# Lightsaber.net
KiCad netlist of a schematic drawn in EasyEDA
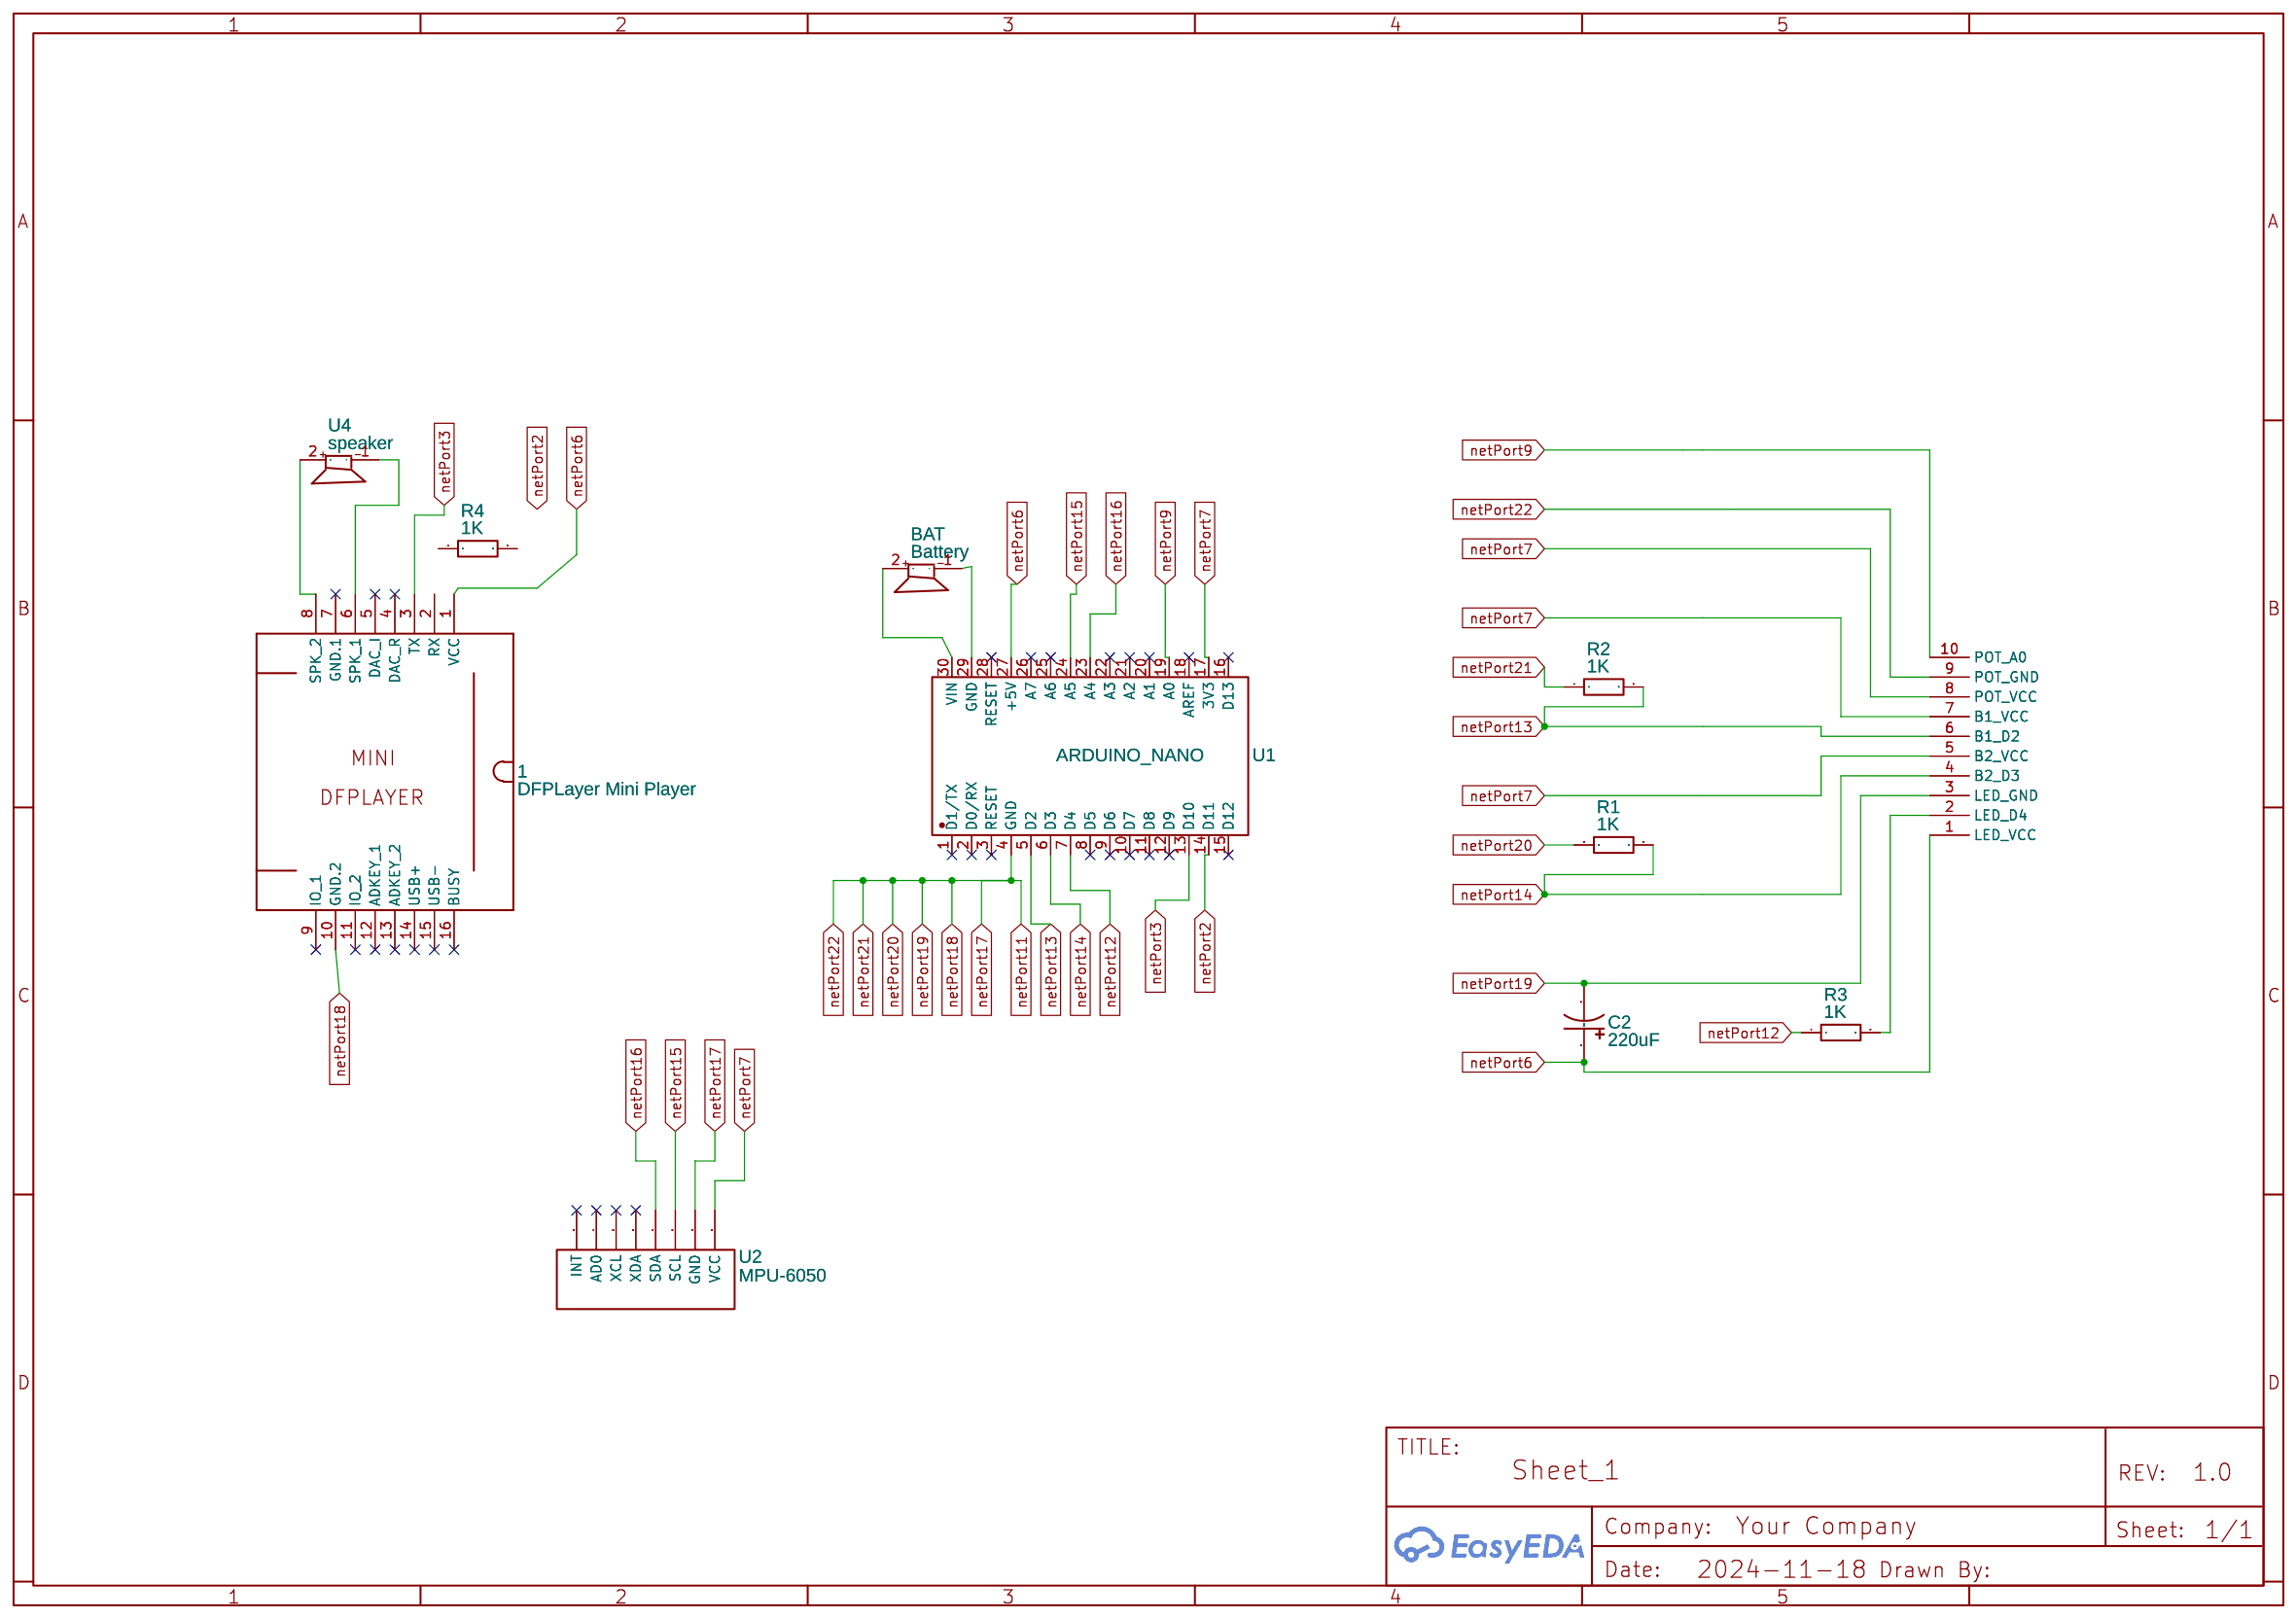
[diagram p0: schematic sheet]

(export (version "E")
  (design (tool "Eeschema 10.0.6"))
  (components
    (comp (ref "1")
      (value "DFPLayer Mini Player")
      (fields (field (name "Manufacturer") "DFP"))
      (libsource (lib "") (part "DFPLayer Mini Player"))
    )
    (comp (ref "BAT") (value "Battery") (libsource (lib "") (part "speaker")))
    (comp (ref "C2") (value "220uF") (libsource (lib "") (part "capacitor 220uF @ 16V")))
    (comp (ref "P1")
      (value "10 pins")
      (fields (field (name "Manufacturer Part") "New SchematicLib"))
      (libsource (lib "") (part "10 pins"))
    )
    (comp (ref "R1")
      (value "1K")
      (fields (field (name "Manufacturer Part") "0.125Wt_k"))
      (libsource (lib "") (part "0.125Wt_d"))
    )
    (comp (ref "R2")
      (value "1K")
      (fields (field (name "Manufacturer Part") "0.125Wt_k"))
      (libsource (lib "") (part "0.125Wt_d"))
    )
    (comp (ref "R3")
      (value "1K")
      (fields (field (name "Manufacturer Part") "0.125Wt_k"))
      (libsource (lib "") (part "0.125Wt_d"))
    )
    (comp (ref "R4")
      (value "1K")
      (fields (field (name "Manufacturer Part") "0.125Wt_k"))
      (libsource (lib "") (part "0.125Wt_d"))
    )
    (comp (ref "U1") (value "ARDUINO_NANO") (libsource (lib "") (part "ARDUINO_NANO")))
    (comp (ref "U2") (value "MPU-6050") (libsource (lib "") (part "MPU-6050")))
    (comp (ref "U4") (value "speaker") (libsource (lib "") (part "speaker_1")))
  )
  (nets
    (net (code "1") (name "Net-(1-SPK_1)") (class "Default")
      (node (ref "1") (pin "6") (pinfunction "SPK_1_6") (pintype "bidirectional"))
      (node (ref "U4") (pin "1") (pinfunction "-_1") (pintype "unspecified"))
    )
    (net (code "2") (name "Net-(1-SPK_2)") (class "Default")
      (node (ref "1") (pin "8") (pinfunction "SPK_2_8") (pintype "bidirectional"))
      (node (ref "U4") (pin "2") (pinfunction "+_2") (pintype "unspecified"))
    )
    (net (code "3") (name "Net-(BAT-+)") (class "Default")
      (node (ref "BAT") (pin "2") (pinfunction "+_2") (pintype "unspecified"))
      (node (ref "U1") (pin "30") (pinfunction "VIN_30") (pintype "unspecified"))
    )
    (net (code "4") (name "Net-(BAT--)") (class "Default")
      (node (ref "BAT") (pin "1") (pinfunction "-_1") (pintype "unspecified"))
      (node (ref "U1") (pin "29") (pinfunction "GND_29") (pintype "unspecified"))
    )
    (net (code "5") (name "Net-(P1-LED_D4)") (class "Default")
      (node (ref "P1") (pin "2") (pinfunction "LED_D4_2") (pintype "unspecified"))
      (node (ref "R3") (pin "2") (pinfunction "2_2") (pintype "unspecified"))
    )
    (net (code "6") (name "netPort2") (class "Default")
      (node (ref "U1") (pin "14") (pinfunction "D11_14") (pintype "unspecified"))
    )
    (net (code "7") (name "netPort3") (class "Default")
      (node (ref "1") (pin "3") (pinfunction "TX_3") (pintype "bidirectional"))
      (node (ref "U1") (pin "13") (pinfunction "D10_13") (pintype "unspecified"))
    )
    (net (code "8") (name "netPort6") (class "Default")
      (node (ref "1") (pin "1") (pinfunction "VCC_1") (pintype "bidirectional"))
      (node (ref "C2") (pin "1") (pinfunction "1_1") (pintype "unspecified"))
      (node (ref "P1") (pin "1") (pinfunction "LED_VCC_1") (pintype "unspecified"))
      (node (ref "U1") (pin "27") (pinfunction "+5V_27") (pintype "unspecified"))
    )
    (net (code "9") (name "netPort7") (class "Default")
      (node (ref "P1") (pin "5") (pinfunction "B2_VCC_5") (pintype "unspecified"))
      (node (ref "P1") (pin "7") (pinfunction "B1_VCC_7") (pintype "unspecified"))
      (node (ref "P1") (pin "8") (pinfunction "POT_VCC_8") (pintype "unspecified"))
      (node (ref "U1") (pin "17") (pinfunction "3V3_17") (pintype "unspecified"))
      (node (ref "U2") (pin "1") (pinfunction "VCC_1") (pintype "unspecified"))
    )
    (net (code "10") (name "netPort9") (class "Default")
      (node (ref "P1") (pin "10") (pinfunction "POT_A0_10") (pintype "unspecified"))
      (node (ref "U1") (pin "19") (pinfunction "A0_19") (pintype "unspecified"))
    )
    (net (code "11") (name "netPort11") (class "Default")
      (node (ref "1") (pin "10") (pinfunction "GND.2_10") (pintype "bidirectional"))
      (node (ref "C2") (pin "2") (pinfunction "2_2") (pintype "unspecified"))
      (node (ref "P1") (pin "3") (pinfunction "LED_GND_3") (pintype "unspecified"))
      (node (ref "P1") (pin "9") (pinfunction "POT_GND_9") (pintype "unspecified"))
      (node (ref "R1") (pin "1") (pinfunction "1_1") (pintype "unspecified"))
      (node (ref "R2") (pin "1") (pinfunction "1_1") (pintype "unspecified"))
      (node (ref "U1") (pin "4") (pinfunction "GND_4") (pintype "unspecified"))
      (node (ref "U2") (pin "2") (pinfunction "GND_2") (pintype "unspecified"))
    )
    (net (code "12") (name "netPort12") (class "Default")
      (node (ref "R3") (pin "1") (pinfunction "1_1") (pintype "unspecified"))
      (node (ref "U1") (pin "7") (pinfunction "D4_7") (pintype "unspecified"))
    )
    (net (code "13") (name "netPort13") (class "Default")
      (node (ref "P1") (pin "6") (pinfunction "B1_D2_6") (pintype "unspecified"))
      (node (ref "R2") (pin "2") (pinfunction "2_2") (pintype "unspecified"))
      (node (ref "U1") (pin "5") (pinfunction "D2_5") (pintype "unspecified"))
    )
    (net (code "14") (name "netPort14") (class "Default")
      (node (ref "P1") (pin "4") (pinfunction "B2_D3_4") (pintype "unspecified"))
      (node (ref "R1") (pin "2") (pinfunction "2_2") (pintype "unspecified"))
      (node (ref "U1") (pin "6") (pinfunction "D3_6") (pintype "unspecified"))
    )
    (net (code "15") (name "netPort15") (class "Default")
      (node (ref "U1") (pin "24") (pinfunction "A5_24") (pintype "unspecified"))
      (node (ref "U2") (pin "3") (pinfunction "SCL_3") (pintype "unspecified"))
    )
    (net (code "16") (name "netPort16") (class "Default")
      (node (ref "U1") (pin "23") (pinfunction "A4_23") (pintype "unspecified"))
      (node (ref "U2") (pin "4") (pinfunction "SDA_4") (pintype "unspecified"))
    )
    (net (code "17") (name "unconnected-(1-ADKEY_1-Pad12)") (class "Default")
      (node (ref "1") (pin "12") (pinfunction "ADKEY_1_12") (pintype "bidirectional+no_connect"))
    )
    (net (code "18") (name "unconnected-(1-ADKEY_2-Pad13)") (class "Default")
      (node (ref "1") (pin "13") (pinfunction "ADKEY_2_13") (pintype "bidirectional+no_connect"))
    )
    (net (code "19") (name "unconnected-(1-BUSY-Pad16)") (class "Default")
      (node (ref "1") (pin "16") (pinfunction "BUSY_16") (pintype "bidirectional+no_connect"))
    )
    (net (code "20") (name "unconnected-(1-DAC_I-Pad5)") (class "Default")
      (node (ref "1") (pin "5") (pinfunction "DAC_I_5") (pintype "bidirectional+no_connect"))
    )
    (net (code "21") (name "unconnected-(1-DAC_R-Pad4)") (class "Default")
      (node (ref "1") (pin "4") (pinfunction "DAC_R_4") (pintype "bidirectional+no_connect"))
    )
    (net (code "22") (name "unconnected-(1-GND.1-Pad7)") (class "Default")
      (node (ref "1") (pin "7") (pinfunction "GND.1_7") (pintype "bidirectional+no_connect"))
    )
    (net (code "23") (name "unconnected-(1-IO_1-Pad9)") (class "Default")
      (node (ref "1") (pin "9") (pinfunction "IO_1_9") (pintype "bidirectional+no_connect"))
    )
    (net (code "24") (name "unconnected-(1-IO_2-Pad11)") (class "Default")
      (node (ref "1") (pin "11") (pinfunction "IO_2_11") (pintype "bidirectional+no_connect"))
    )
    (net (code "25") (name "unconnected-(1-RX-Pad2)") (class "Default")
      (node (ref "1") (pin "2") (pinfunction "RX_2") (pintype "bidirectional"))
    )
    (net (code "26") (name "unconnected-(1-USB+-Pad14)") (class "Default")
      (node (ref "1") (pin "14") (pinfunction "USB+_14") (pintype "bidirectional+no_connect"))
    )
    (net (code "27") (name "unconnected-(1-USB--Pad15)") (class "Default")
      (node (ref "1") (pin "15") (pinfunction "USB-_15") (pintype "bidirectional+no_connect"))
    )
    (net (code "28") (name "unconnected-(R4-Pad1)") (class "Default")
      (node (ref "R4") (pin "1") (pinfunction "1_1") (pintype "unspecified"))
    )
    (net (code "29") (name "unconnected-(R4-Pad2)") (class "Default")
      (node (ref "R4") (pin "2") (pinfunction "2_2") (pintype "unspecified"))
    )
    (net (code "30") (name "unconnected-(U1-A1-Pad20)") (class "Default")
      (node (ref "U1") (pin "20") (pinfunction "A1_20") (pintype "unspecified+no_connect"))
    )
    (net (code "31") (name "unconnected-(U1-A2-Pad21)") (class "Default")
      (node (ref "U1") (pin "21") (pinfunction "A2_21") (pintype "unspecified+no_connect"))
    )
    (net (code "32") (name "unconnected-(U1-A3-Pad22)") (class "Default")
      (node (ref "U1") (pin "22") (pinfunction "A3_22") (pintype "unspecified+no_connect"))
    )
    (net (code "33") (name "unconnected-(U1-A6-Pad25)") (class "Default")
      (node (ref "U1") (pin "25") (pinfunction "A6_25") (pintype "unspecified+no_connect"))
    )
    (net (code "34") (name "unconnected-(U1-A7-Pad26)") (class "Default")
      (node (ref "U1") (pin "26") (pinfunction "A7_26") (pintype "unspecified+no_connect"))
    )
    (net (code "35") (name "unconnected-(U1-AREF-Pad18)") (class "Default")
      (node (ref "U1") (pin "18") (pinfunction "AREF_18") (pintype "unspecified+no_connect"))
    )
    (net (code "36") (name "unconnected-(U1-D0{slash}RX-Pad2)") (class "Default")
      (node (ref "U1") (pin "2") (pinfunction "D0/RX_2") (pintype "unspecified+no_connect"))
    )
    (net (code "37") (name "unconnected-(U1-D1{slash}TX-Pad1)") (class "Default")
      (node (ref "U1") (pin "1") (pinfunction "D1/TX_1") (pintype "unspecified+no_connect"))
    )
    (net (code "38") (name "unconnected-(U1-D5-Pad8)") (class "Default")
      (node (ref "U1") (pin "8") (pinfunction "D5_8") (pintype "unspecified+no_connect"))
    )
    (net (code "39") (name "unconnected-(U1-D6-Pad9)") (class "Default")
      (node (ref "U1") (pin "9") (pinfunction "D6_9") (pintype "unspecified+no_connect"))
    )
    (net (code "40") (name "unconnected-(U1-D7-Pad10)") (class "Default")
      (node (ref "U1") (pin "10") (pinfunction "D7_10") (pintype "unspecified+no_connect"))
    )
    (net (code "41") (name "unconnected-(U1-D8-Pad11)") (class "Default")
      (node (ref "U1") (pin "11") (pinfunction "D8_11") (pintype "unspecified+no_connect"))
    )
    (net (code "42") (name "unconnected-(U1-D9-Pad12)") (class "Default")
      (node (ref "U1") (pin "12") (pinfunction "D9_12") (pintype "unspecified+no_connect"))
    )
    (net (code "43") (name "unconnected-(U1-D12-Pad15)") (class "Default")
      (node (ref "U1") (pin "15") (pinfunction "D12_15") (pintype "unspecified+no_connect"))
    )
    (net (code "44") (name "unconnected-(U1-D13-Pad16)") (class "Default")
      (node (ref "U1") (pin "16") (pinfunction "D13_16") (pintype "unspecified+no_connect"))
    )
    (net (code "45") (name "unconnected-(U1-RESET-Pad3)") (class "Default")
      (node (ref "U1") (pin "3") (pinfunction "RESET_3") (pintype "unspecified+no_connect"))
    )
    (net (code "46") (name "unconnected-(U1-RESET-Pad28)") (class "Default")
      (node (ref "U1") (pin "28") (pinfunction "RESET_28") (pintype "unspecified+no_connect"))
    )
    (net (code "47") (name "unconnected-(U2-AD0-Pad7)") (class "Default")
      (node (ref "U2") (pin "7") (pinfunction "AD0_7") (pintype "unspecified+no_connect"))
    )
    (net (code "48") (name "unconnected-(U2-INT-Pad8)") (class "Default")
      (node (ref "U2") (pin "8") (pinfunction "INT_8") (pintype "unspecified+no_connect"))
    )
    (net (code "49") (name "unconnected-(U2-XCL-Pad6)") (class "Default")
      (node (ref "U2") (pin "6") (pinfunction "XCL_6") (pintype "unspecified+no_connect"))
    )
    (net (code "50") (name "unconnected-(U2-XDA-Pad5)") (class "Default")
      (node (ref "U2") (pin "5") (pinfunction "XDA_5") (pintype "unspecified+no_connect"))
    )
  )
)
